# INTERNAL_REGULATORS.net
KiCad netlist of a schematic drawn in Altium Designer
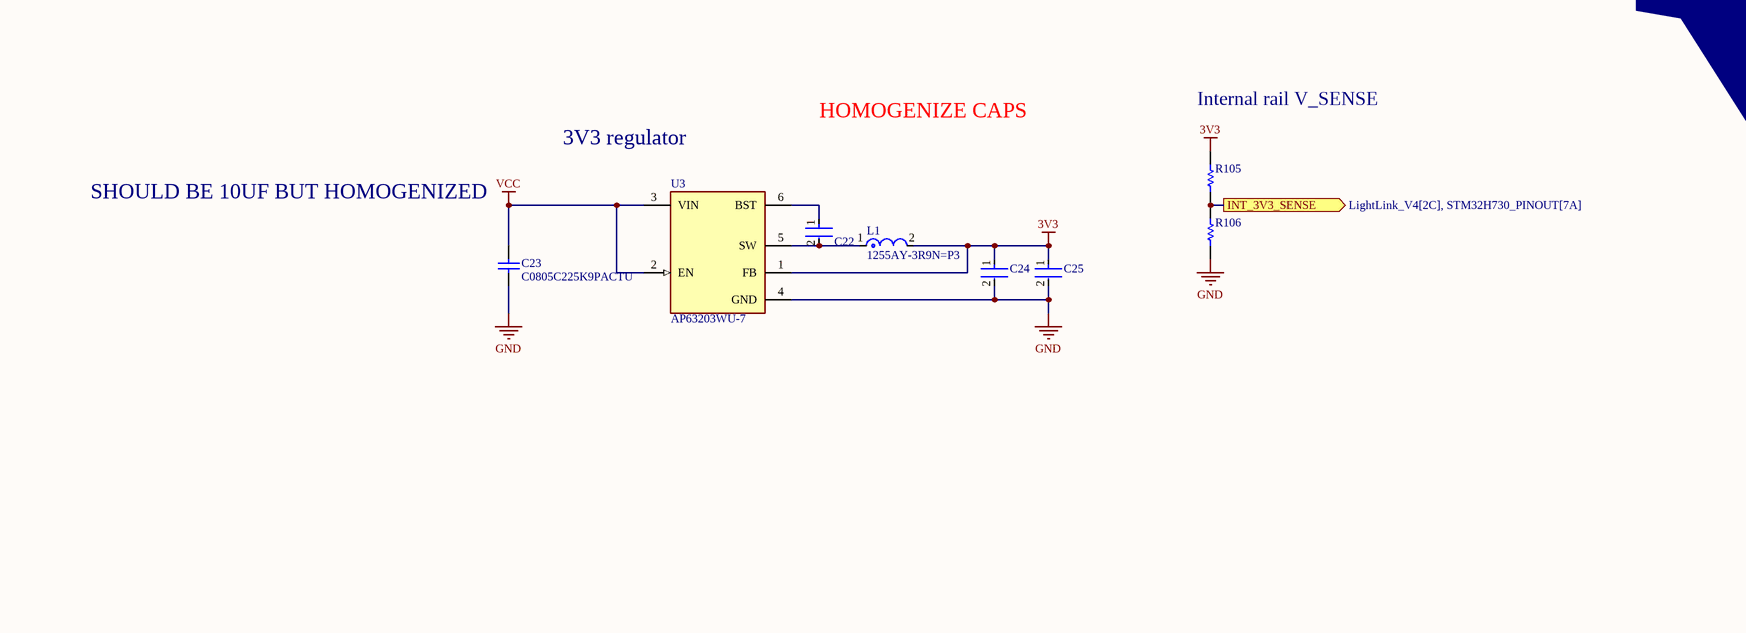
[diagram p0: INTERNAL_REGULATORS.SchDoc, top left]
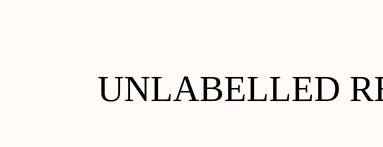
[diagram p1: INTERNAL_REGULATORS.SchDoc, bottom middle]

(export (version "E")
  (design (tool "Eeschema 10.0.6"))
  (components
    (comp (ref "C22")
      (value "C0402C104K8PACTU")
      (footprint "FP-C0402-BB-MFG")
      (description "CAP CER 0.1UF 10V X5R 0402")
      (fields (field (name "MANUFACTURER") "Kemet") (field (name "TOLERANCE") "0.1"))
      (libsource (lib "Altium Content Vault") (part "b4654b650e69147ec39a6b967a45e02"))
    )
    (comp (ref "C23")
      (value "C0805C225K9PACTU")
      (footprint "CAPC2013X145X50ML20T25")
      (fields (field (name "MANUFACTURER") "Kemet"))
      (libsource (lib "Altium Content Vault") (part "CAP"))
    )
    (comp (ref "C24")
      (value "GRM21BR61E226ME44L")
      (footprint "FP-GRM21B-0_2-e0_2_0_7-IPC_B")
      (description "Chip Multilayer Ceramic Capacitors for General Purpose, 0805, 22uF, X5R, 15%, 20%, 25V")
      (fields (field (name "TOLERANCE") "20%") (field (name "VOLTAGE") "25V"))
      (libsource (lib "Altium Content Vault") (part "b4654b650e69147ec39a6b967a45e02"))
    )
    (comp (ref "C25")
      (value "GRM21BR61E226ME44L")
      (footprint "FP-GRM21B-0_2-e0_2_0_7-IPC_B")
      (description "Chip Multilayer Ceramic Capacitors for General Purpose, 0805, 22uF, X5R, 15%, 20%, 25V")
      (fields (field (name "TOLERANCE") "20%") (field (name "VOLTAGE") "25V"))
      (libsource (lib "Altium Content Vault") (part "b4654b650e69147ec39a6b967a45e02"))
    )
    (comp (ref "L1")
      (value "1255AY-3R9N=P3")
      (footprint "FP-DG6045C-MFG")
      (description "Shielded Wirewound Inductor 3.9uH 30% 4200mA 0.0264Ω SMD")
      (fields (field (name "TOLERANCE") "30%"))
      (libsource (lib "Altium Content Vault") (part "4cc4b267dca4c8e51f7102f422741d8"))
    )
    (comp (ref "R105")
      (value "ERJ3EKF1002V")
      (footprint "RESC1609X55X30LL15T15")
      (description "Chip Resistor, 10 KOhm, +/- 1%, 0.1 W, -55 to 155 degC, 0603 (1608 Metric), RoHS, Tape and Reel")
      (fields (field (name "TOLERANCE") "1%") (field (name "MANUFACTURER") "Panasonic"))
      (libsource (lib "Altium Content Vault") (part "RES-2"))
    )
    (comp (ref "R106")
      (value "ERJ3EKF1002V")
      (footprint "RESC1609X55X30LL15T15")
      (description "Chip Resistor, 10 KOhm, +/- 1%, 0.1 W, -55 to 155 degC, 0603 (1608 Metric), RoHS, Tape and Reel")
      (fields (field (name "TOLERANCE") "1%") (field (name "MANUFACTURER") "Panasonic"))
      (libsource (lib "Altium Content Vault") (part "RES-2"))
    )
    (comp (ref "U3")
      (value "AP63203WU-7")
      (footprint "FP-TSOT26-MFG")
      (description "IC REG BUCK 3.3V 2A TSOT26")
      (fields
        (field (name "MANUFACTURER") "Diodes Inc.")
        (field (name "OCTOPART") "https://octopart.com/ap63203wu-7-diodes+inc.-98099550")
      )
      (libsource (lib "Altium Content Vault") (part "0e61c2974d7114b43f01ef96ae2e524"))
    )
  )
  (nets
    (net (code "1") (name "/INT_3V3_SENSE") (class "Default")
      (node (ref "R105") (pin "1") (pinfunction "1_1") (pintype "passive"))
      (node (ref "R106") (pin "2") (pinfunction "2_2") (pintype "passive"))
    )
    (net (code "2") (name "3V3") (class "Default")
      (node (ref "C24") (pin "1") (pinfunction "1_1") (pintype "passive"))
      (node (ref "C25") (pin "1") (pinfunction "1_1") (pintype "passive"))
      (node (ref "L1") (pin "2") (pinfunction "2_2") (pintype "passive"))
      (node (ref "R105") (pin "2") (pinfunction "2_2") (pintype "passive"))
      (node (ref "U3") (pin "1") (pinfunction "FB_1") (pintype "passive"))
    )
    (net (code "3") (name "GND") (class "Default")
      (node (ref "C23") (pin "1") (pinfunction "1_1") (pintype "passive"))
      (node (ref "C24") (pin "2") (pinfunction "2_2") (pintype "passive"))
      (node (ref "C25") (pin "2") (pinfunction "2_2") (pintype "passive"))
      (node (ref "R106") (pin "1") (pinfunction "1_1") (pintype "passive"))
      (node (ref "U3") (pin "4") (pinfunction "GND_4") (pintype "power_in"))
    )
    (net (code "4") (name "Net-(U3-BST)") (class "Default")
      (node (ref "C22") (pin "1") (pinfunction "1_1") (pintype "passive"))
      (node (ref "U3") (pin "6") (pinfunction "BST_6") (pintype "passive"))
    )
    (net (code "5") (name "Net-(U3-SW)") (class "Default")
      (node (ref "C22") (pin "2") (pinfunction "2_2") (pintype "passive"))
      (node (ref "L1") (pin "1") (pinfunction "1_1") (pintype "passive"))
      (node (ref "U3") (pin "5") (pinfunction "SW_5") (pintype "passive"))
    )
    (net (code "6") (name "VCC") (class "Default")
      (node (ref "C23") (pin "2") (pinfunction "2_2") (pintype "passive"))
      (node (ref "U3") (pin "2") (pinfunction "EN_2") (pintype "input"))
      (node (ref "U3") (pin "3") (pinfunction "VIN_3") (pintype "power_in"))
    )
  )
)
